# PiTlnfo.net
KiCad netlist of a schematic drawn in EAGLE
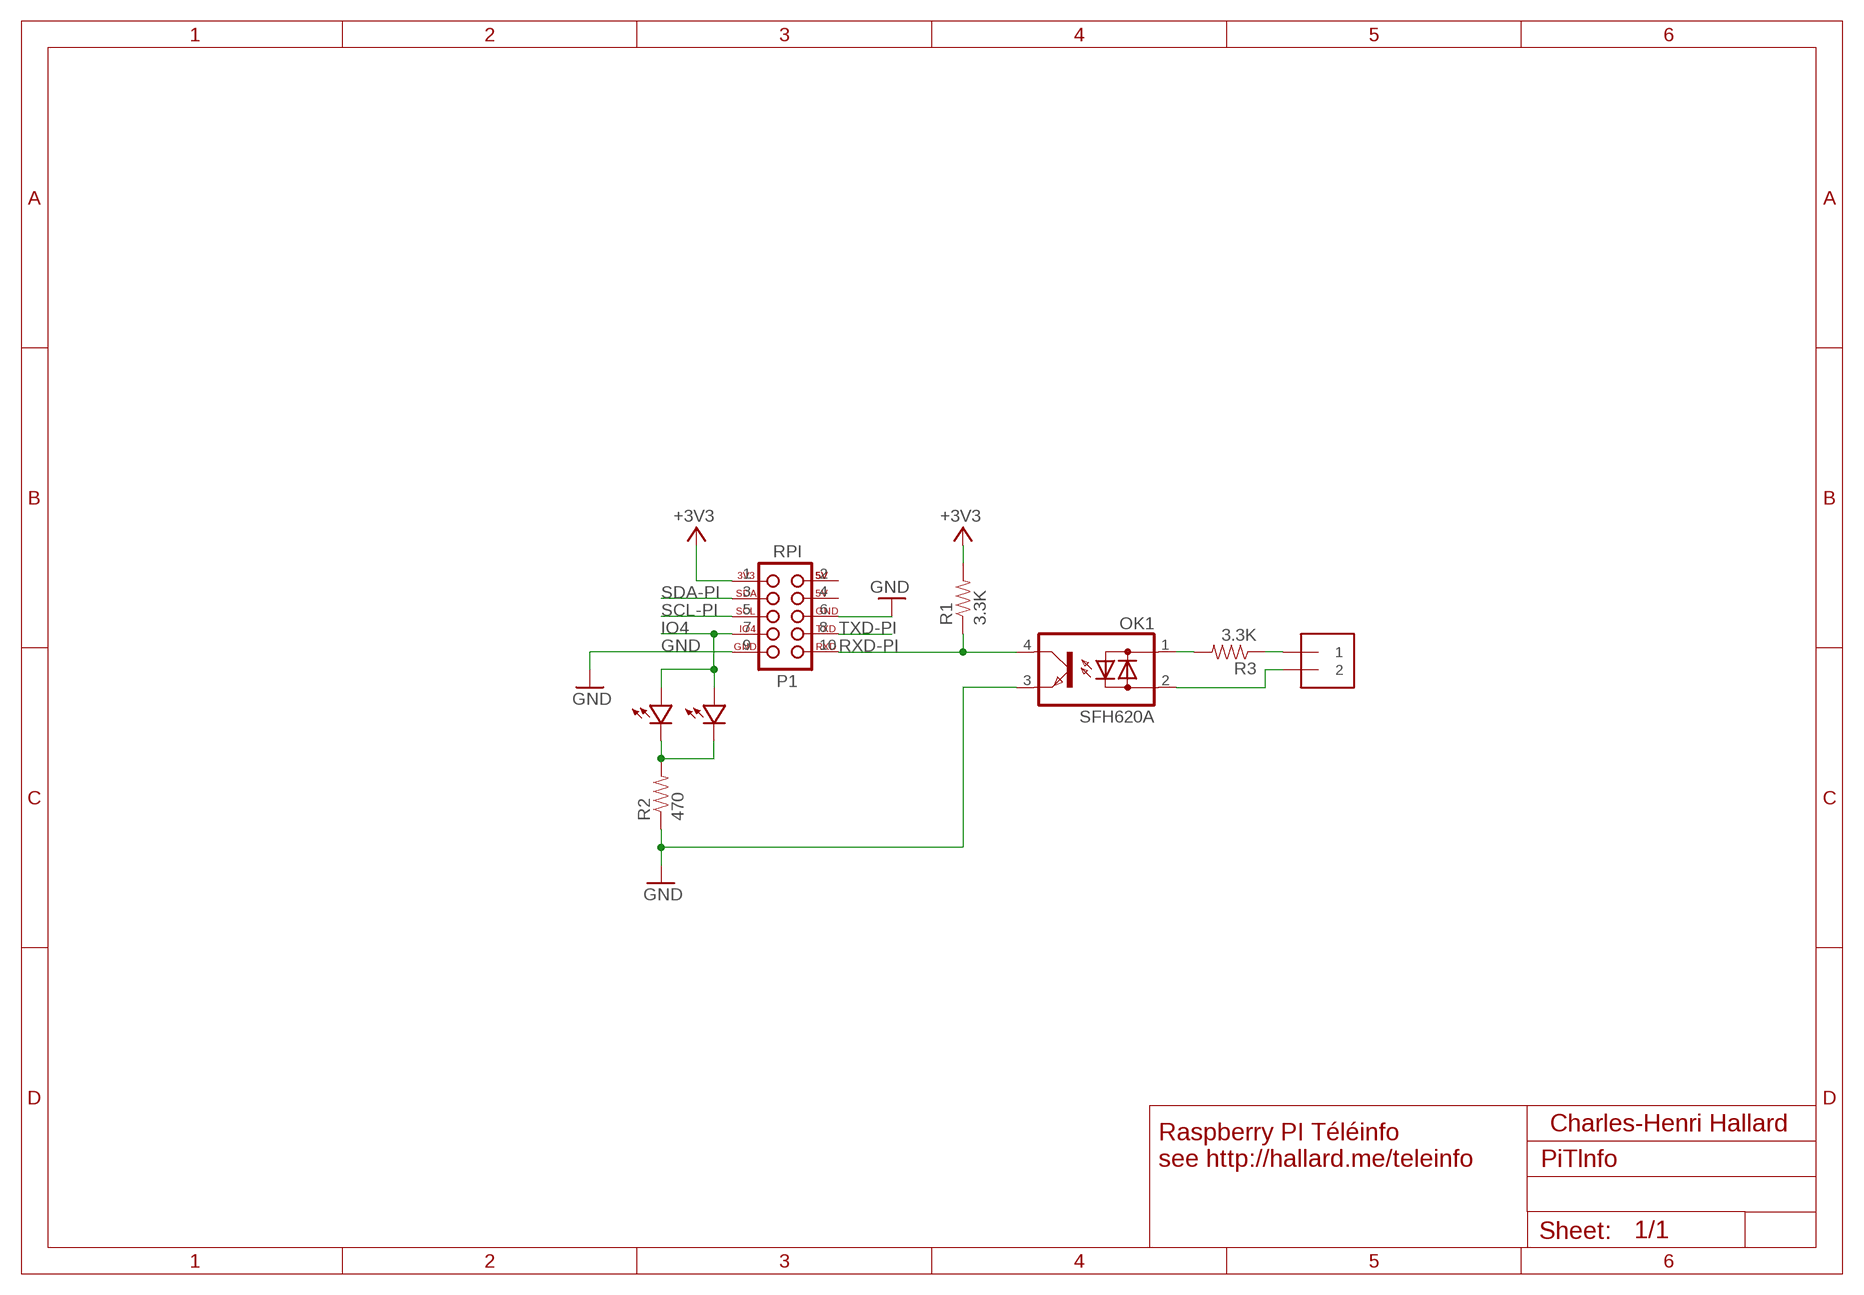
[diagram p0: schematic, sheet 1]

(export (version "E")
  (design (tool "Eeschema 10.0.6"))
  (components
    (comp (ref "J1")
      (value "1X2-3.5MM")
      (footprint "eagle-import:1X2-3.5MM")
      (libsource (lib "eagle-import") (part "1X2-3.5MM"))
    )
    (comp (ref "LED1")
      (value "LED0805-LARGE")
      (footprint "eagle-import:0805-LED-LARGEPADS")
      (libsource (lib "eagle-import") (part "LED0805-LARGE"))
    )
    (comp (ref "LED3")
      (value "LED3MM")
      (footprint "eagle-import:LED3MM")
      (libsource (lib "eagle-import") (part "LED3MM"))
    )
    (comp (ref "OK1")
      (value "SFH620A")
      (footprint "eagle-import:DIL04")
      (fields (field (name "MPN") "SFH620A-2"))
      (libsource (lib "eagle-import") (part "SFH620A"))
    )
    (comp (ref "R1")
      (value "3.3K")
      (footprint "eagle-import:AXIAL-0.3-KIT")
      (libsource (lib "eagle-import") (part "RESISTORKIT"))
    )
    (comp (ref "R2")
      (value "470")
      (footprint "eagle-import:AXIAL-0.3-KIT")
      (libsource (lib "eagle-import") (part "RESISTORKIT"))
    )
    (comp (ref "R3")
      (value "3.3K")
      (footprint "eagle-import:AXIAL-0.3-KIT")
      (libsource (lib "eagle-import") (part "RESISTORKIT"))
    )
    (comp (ref "U$2")
      (value "RASPBERRY_PI_2X5")
      (footprint "eagle-import:2X05_LOCK")
      (libsource (lib "eagle-import") (part "RASPBERRY_PI_2X5"))
    )
  )
  (nets
    (net (code "1") (name "+3V3") (class "Default")
      (node (ref "R1") (pin "P$2") (pinfunction "2_P$2") (pintype "passive"))
      (node (ref "U$2") (pin "1") (pinfunction "1_1") (pintype "power_in"))
    )
    (net (code "2") (name "/2") (class "Default")
      (node (ref "U$2") (pin "2") (pinfunction "2_2") (pintype "power_in"))
    )
    (net (code "3") (name "/4") (class "Default")
      (node (ref "U$2") (pin "4") (pinfunction "4_4") (pintype "power_in"))
    )
    (net (code "4") (name "/IO4") (class "Default")
      (node (ref "LED1") (pin "PLUS") (pinfunction "PLUS_PLUS") (pintype "passive"))
      (node (ref "LED3") (pin "PLUS") (pinfunction "PLUS_PLUS") (pintype "passive"))
      (node (ref "U$2") (pin "7") (pinfunction "7_7") (pintype "bidirectional"))
    )
    (net (code "5") (name "/RXD-PI") (class "Default")
      (node (ref "OK1") (pin "4") (pinfunction "C_4") (pintype "passive"))
      (node (ref "R1") (pin "P$1") (pinfunction "1_P$1") (pintype "passive"))
      (node (ref "U$2") (pin "10") (pinfunction "10_10") (pintype "input"))
    )
    (net (code "6") (name "/SCL-PI") (class "Default")
      (node (ref "U$2") (pin "5") (pinfunction "5_5") (pintype "bidirectional"))
    )
    (net (code "7") (name "/SDA-PI") (class "Default")
      (node (ref "U$2") (pin "3") (pinfunction "3_3") (pintype "bidirectional"))
    )
    (net (code "8") (name "/TXD-PI") (class "Default")
      (node (ref "U$2") (pin "8") (pinfunction "8_8") (pintype "output"))
    )
    (net (code "9") (name "GND") (class "Default")
      (node (ref "OK1") (pin "3") (pinfunction "E_3") (pintype "passive"))
      (node (ref "R2") (pin "P$1") (pinfunction "1_P$1") (pintype "passive"))
      (node (ref "U$2") (pin "6") (pinfunction "6_6") (pintype "passive"))
      (node (ref "U$2") (pin "9") (pinfunction "9_9") (pintype "passive"))
    )
    (net (code "10") (name "Net-(OK1-AC1)") (class "Default")
      (node (ref "OK1") (pin "1") (pinfunction "AC1_1") (pintype "passive"))
      (node (ref "R3") (pin "P$2") (pinfunction "2_P$2") (pintype "passive"))
    )
    (net (code "11") (name "Net-(OK1-AC2)") (class "Default")
      (node (ref "J1") (pin "2") (pinfunction "2_2") (pintype "passive"))
      (node (ref "OK1") (pin "2") (pinfunction "AC2_2") (pintype "passive"))
    )
    (net (code "12") (name "Net-(R2-2)") (class "Default")
      (node (ref "LED1") (pin "MINUS") (pinfunction "MINUS_MINUS") (pintype "passive"))
      (node (ref "LED3") (pin "MINUS") (pinfunction "MINUS_MINUS") (pintype "passive"))
      (node (ref "R2") (pin "P$2") (pinfunction "2_P$2") (pintype "passive"))
    )
    (net (code "13") (name "Net-(R3-1)") (class "Default")
      (node (ref "J1") (pin "1") (pinfunction "1_1") (pintype "passive"))
      (node (ref "R3") (pin "P$1") (pinfunction "1_P$1") (pintype "passive"))
    )
  )
)
